# Power.net
KiCad netlist of a schematic drawn in Altium Designer
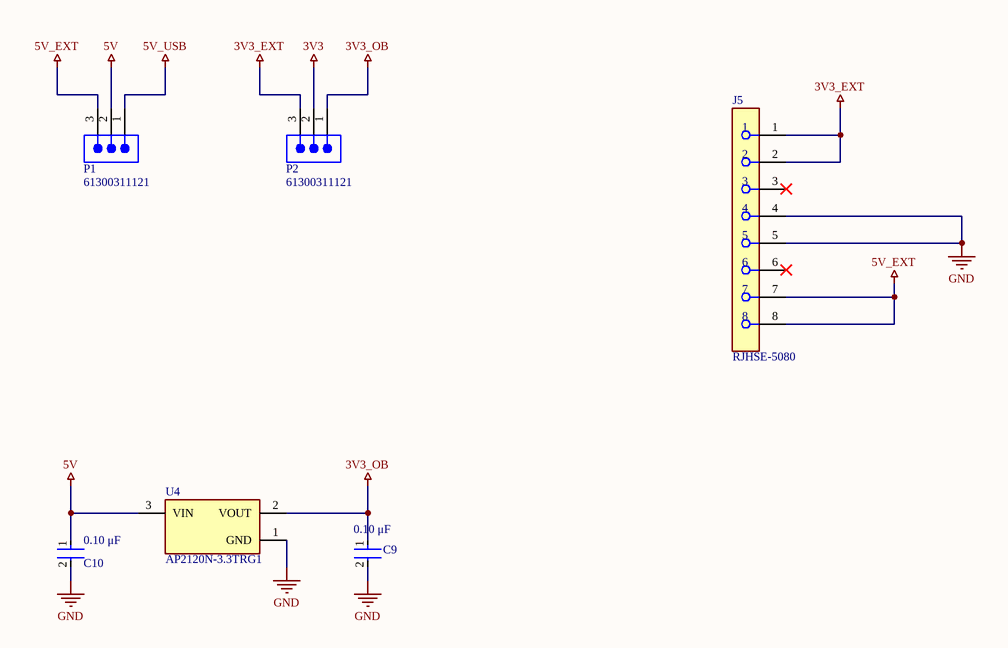
[diagram p0: Power.SchDoc]

(export (version "E")
  (design (tool "Eeschema 10.0.6"))
  (components
    (comp (ref "C9")
      (value "C0603C104K5RACTU")
      (footprint "FP-C0603C-CF-MFG")
      (description "CAP CER 0.1UF 50V X7R 0603")
      (fields
        (field (name "TOLERANCE") "0.1")
        (field (name "MANUFACTURER") "KEMET")
        (field (name "CAPACITANCE") "0.10 μF")
      )
      (libsource (lib "Altium Content Vault") (part "b4654b650e69147ec39a6b967a45e02"))
    )
    (comp (ref "C10")
      (value "C0603C104K5RACTU")
      (footprint "FP-C0603C-CF-MFG")
      (description "CAP CER 0.1UF 50V X7R 0603")
      (fields
        (field (name "TOLERANCE") "0.1")
        (field (name "MANUFACTURER") "KEMET")
        (field (name "CAPACITANCE") "0.10 μF")
      )
      (libsource (lib "Altium Content Vault") (part "b4654b650e69147ec39a6b967a45e02"))
    )
    (comp (ref "J5")
      (value "RJHSE-5080")
      (footprint "FP-RJHSE-5080-MFG")
      (description "CONN MOD JACK 8P8C R/A UNSHLD")
      (fields
        (field (name "OCTOPART") "https://octopart.com/rjhse-5080-amphenol-45060")
        (field (name "MANUFACTURER") "Amphenol")
      )
      (libsource (lib "Altium Content Vault") (part "b0a0b555dd3abf3683e7c330df25cc4"))
    )
    (comp (ref "P1")
      (value "61300311121")
      (footprint "61300311121")
      (libsource (lib "Altium Content Vault") (part "Header_Male_1R_03P"))
    )
    (comp (ref "P2")
      (value "61300311121")
      (footprint "61300311121")
      (libsource (lib "Altium Content Vault") (part "Header_Male_1R_03P"))
    )
    (comp (ref "U4")
      (value "AP2120N-3.3TRG1")
      (footprint "FP-SOT23-MFG")
      (description "IC REG LINEAR 3.3V 150MA SOT23")
      (fields
        (field (name "MANUFACTURER") "Diodes Inc.")
        (field (name "OCTOPART") "https://octopart.com/ap2120n-3.3trg1-diodes+inc.-30954573")
      )
      (libsource (lib "Altium Content Vault") (part "340b21d0b7389e2ba8b62ca99e39354"))
    )
  )
  (nets
    (net (code "1") (name "3V3") (class "Default")
      (node (ref "P2") (pin "2") (pinfunction "2_2") (pintype "passive"))
    )
    (net (code "2") (name "3V3_EXT") (class "Default")
      (node (ref "J5") (pin "1") (pinfunction "1_1") (pintype "passive"))
      (node (ref "J5") (pin "2") (pinfunction "2_2") (pintype "passive"))
      (node (ref "P2") (pin "3") (pinfunction "3_3") (pintype "passive"))
    )
    (net (code "3") (name "3V3_OB") (class "Default")
      (node (ref "C9") (pin "1") (pinfunction "1_1") (pintype "passive"))
      (node (ref "P2") (pin "1") (pinfunction "1_1") (pintype "passive"))
      (node (ref "U4") (pin "2") (pinfunction "VOUT_2") (pintype "power_in"))
    )
    (net (code "4") (name "5V") (class "Default")
      (node (ref "C10") (pin "1") (pinfunction "1_1") (pintype "passive"))
      (node (ref "P1") (pin "2") (pinfunction "2_2") (pintype "passive"))
      (node (ref "U4") (pin "3") (pinfunction "VIN_3") (pintype "power_in"))
    )
    (net (code "5") (name "5V_EXT") (class "Default")
      (node (ref "J5") (pin "7") (pinfunction "7_7") (pintype "passive"))
      (node (ref "J5") (pin "8") (pinfunction "8_8") (pintype "passive"))
      (node (ref "P1") (pin "3") (pinfunction "3_3") (pintype "passive"))
    )
    (net (code "6") (name "5V_USB") (class "Default")
      (node (ref "P1") (pin "1") (pinfunction "1_1") (pintype "passive"))
    )
    (net (code "7") (name "GND") (class "Default")
      (node (ref "C10") (pin "2") (pinfunction "2_2") (pintype "passive"))
      (node (ref "C9") (pin "2") (pinfunction "2_2") (pintype "passive"))
      (node (ref "J5") (pin "4") (pinfunction "4_4") (pintype "passive"))
      (node (ref "J5") (pin "5") (pinfunction "5_5") (pintype "passive"))
      (node (ref "U4") (pin "1") (pinfunction "GND_1") (pintype "power_in"))
    )
    (net (code "8") (name "unconnected-(J5-Pad3)") (class "Default")
      (node (ref "J5") (pin "3") (pinfunction "3_3") (pintype "passive+no_connect"))
    )
    (net (code "9") (name "unconnected-(J5-Pad6)") (class "Default")
      (node (ref "J5") (pin "6") (pinfunction "6_6") (pintype "passive+no_connect"))
    )
  )
)
